# Motor_Driver_New_v21.net
KiCad netlist of a schematic drawn in EAGLE
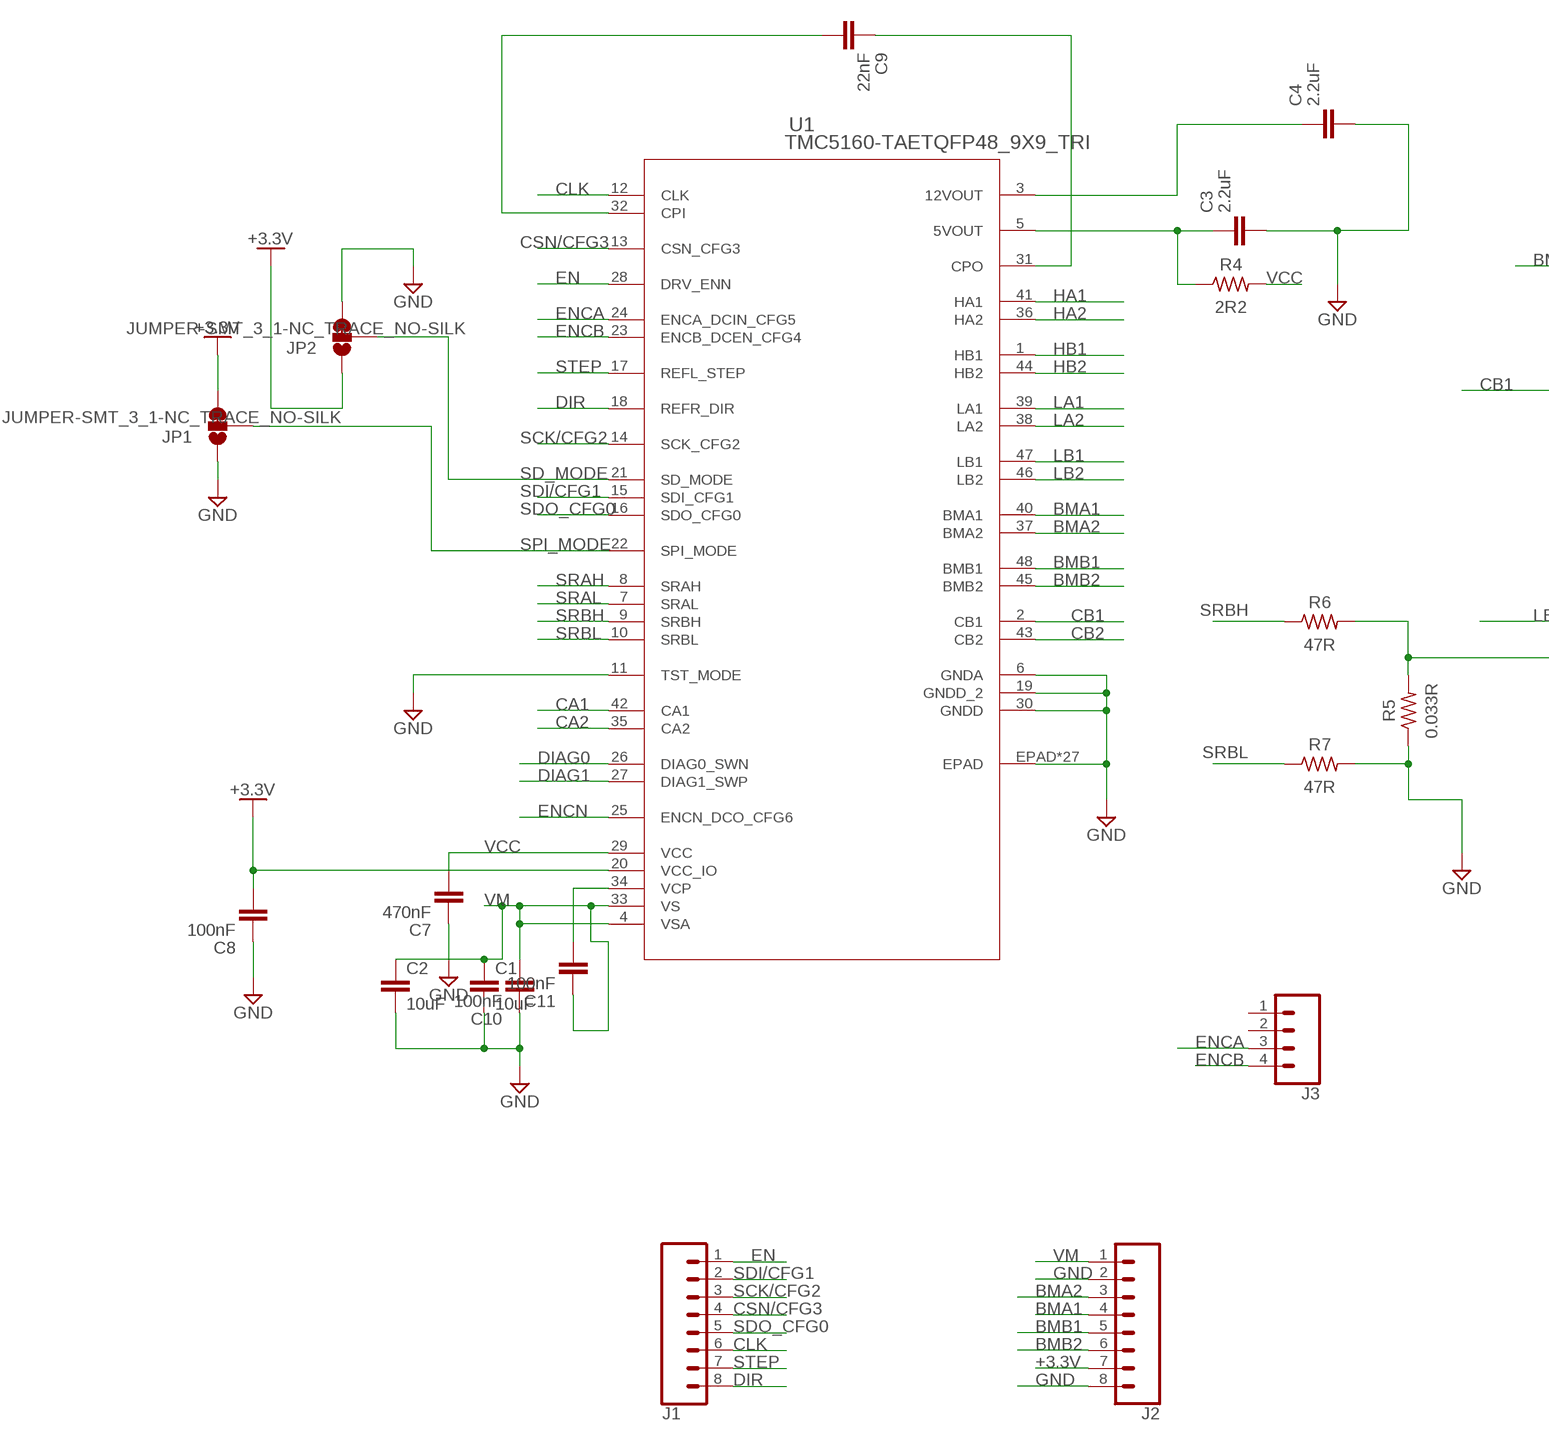
[diagram p0: schematic, sheet 1, part 1 of 2]
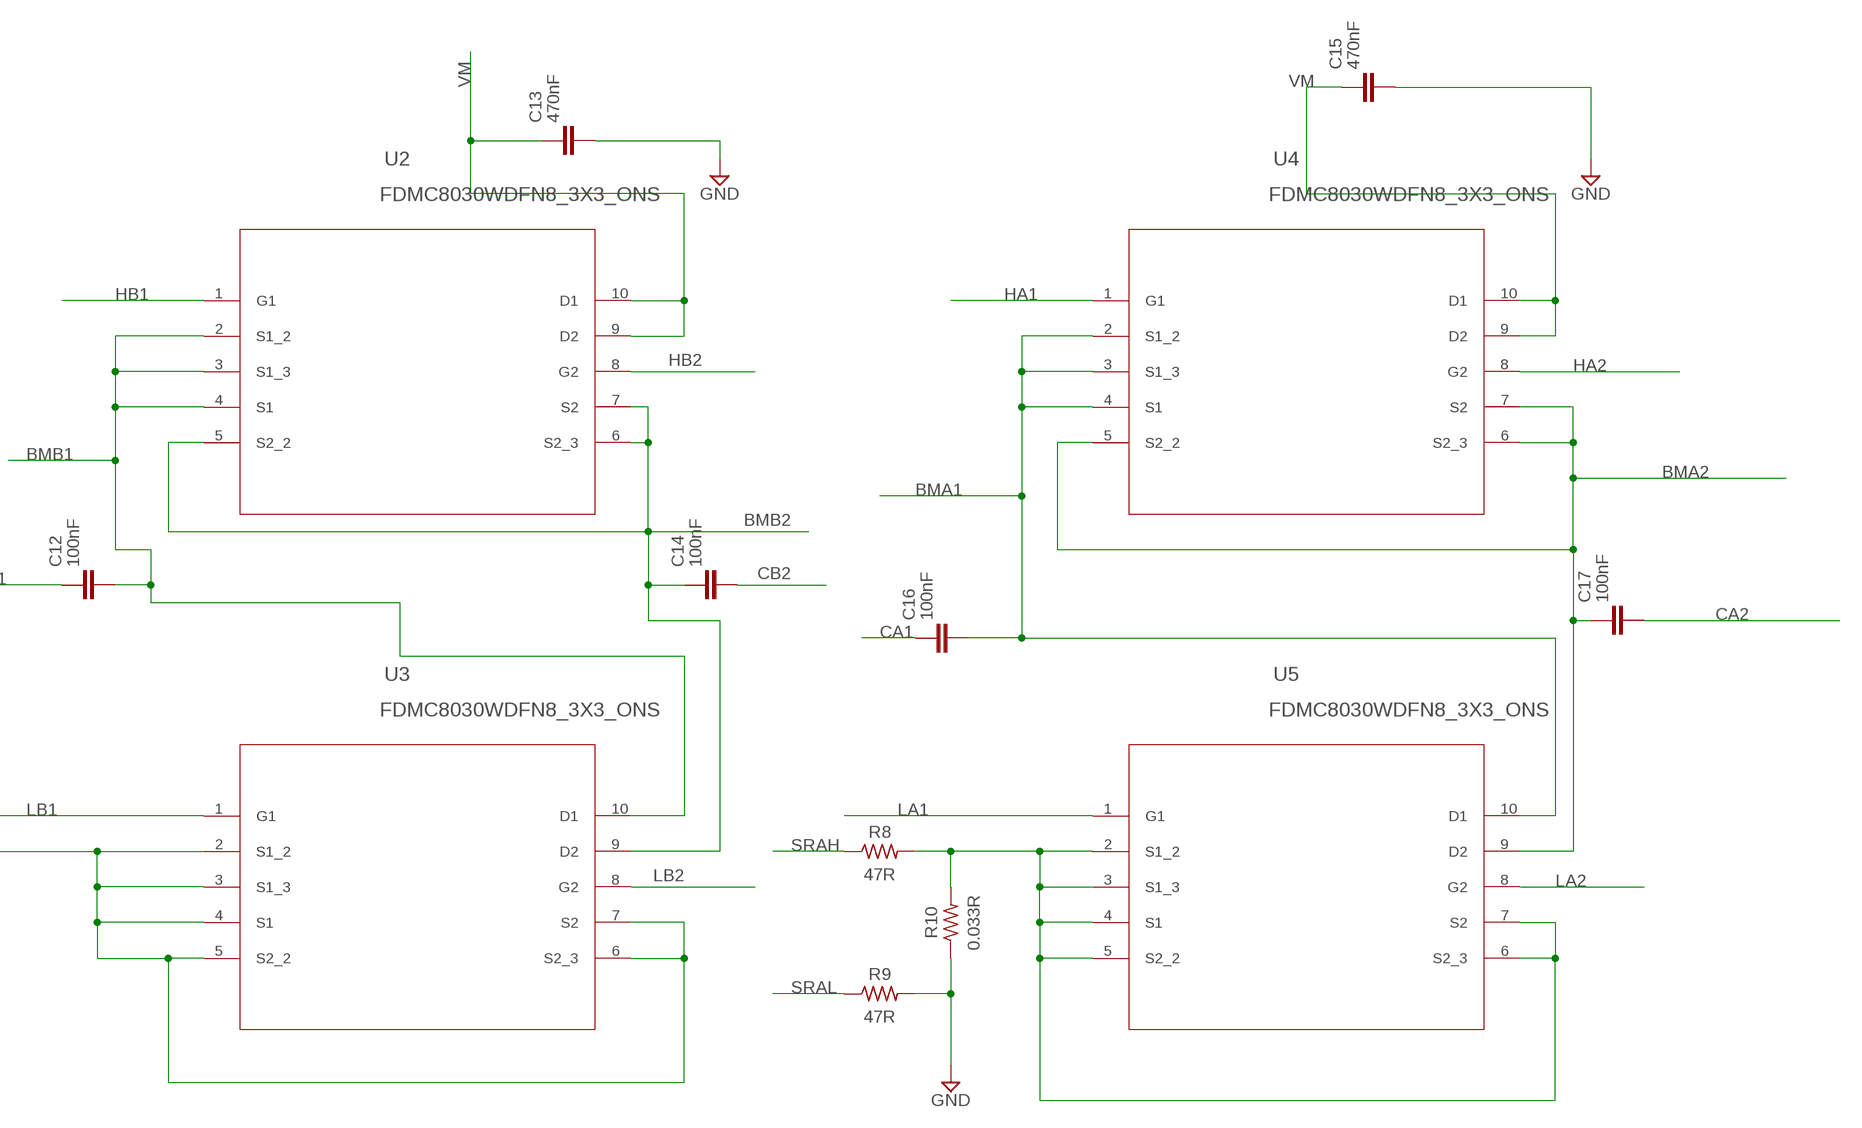
[diagram p1: schematic, sheet 1, part 2 of 2]

(export (version "E")
  (design (tool "Eeschema 10.0.6"))
  (components
    (comp (ref "C1")
      (value "10uF")
      (footprint "eagle-import:0805")
      (libsource (lib "eagle-import") (part "10UF-0805-25V-10%"))
    )
    (comp (ref "C2")
      (value "10uF")
      (footprint "eagle-import:0805")
      (libsource (lib "eagle-import") (part "10UF-0805-25V-10%"))
    )
    (comp (ref "C3")
      (value "2.2uF")
      (footprint "eagle-import:CAPC1005X60")
      (libsource (lib "eagle-import") (part "CCHIP-0402(1005-METRIC)_"))
    )
    (comp (ref "C4")
      (value "2.2uF")
      (footprint "eagle-import:CAPC1005X60")
      (libsource (lib "eagle-import") (part "CCHIP-0402(1005-METRIC)_"))
    )
    (comp (ref "C7")
      (value "470nF")
      (footprint "eagle-import:CAPC1005X60")
      (libsource (lib "eagle-import") (part "CCHIP-0402(1005-METRIC)_"))
    )
    (comp (ref "C8")
      (value "100nF")
      (footprint "eagle-import:CAPC1005X60")
      (libsource (lib "eagle-import") (part "CCHIP-0402(1005-METRIC)_"))
    )
    (comp (ref "C9")
      (value "22nF")
      (footprint "eagle-import:CAPC1005X60")
      (libsource (lib "eagle-import") (part "CCHIP-0402(1005-METRIC)_"))
    )
    (comp (ref "C10")
      (value "100nF")
      (footprint "eagle-import:CAPC1005X60")
      (libsource (lib "eagle-import") (part "CCHIP-0402(1005-METRIC)_"))
    )
    (comp (ref "C11")
      (value "100nF")
      (footprint "eagle-import:CAPC1005X60")
      (libsource (lib "eagle-import") (part "CCHIP-0402(1005-METRIC)_"))
    )
    (comp (ref "C12")
      (value "100nF")
      (footprint "eagle-import:CAPC1005X60")
      (libsource (lib "eagle-import") (part "CCHIP-0402(1005-METRIC)_"))
    )
    (comp (ref "C13")
      (value "470nF")
      (footprint "eagle-import:CAPC1005X60")
      (libsource (lib "eagle-import") (part "CCHIP-0402(1005-METRIC)_"))
    )
    (comp (ref "C14")
      (value "100nF")
      (footprint "eagle-import:CAPC1005X60")
      (libsource (lib "eagle-import") (part "CCHIP-0402(1005-METRIC)_"))
    )
    (comp (ref "C15")
      (value "470nF")
      (footprint "eagle-import:CAPC1005X60")
      (libsource (lib "eagle-import") (part "CCHIP-0402(1005-METRIC)_"))
    )
    (comp (ref "C16")
      (value "100nF")
      (footprint "eagle-import:CAPC1005X60")
      (libsource (lib "eagle-import") (part "CCHIP-0402(1005-METRIC)_"))
    )
    (comp (ref "C17")
      (value "100nF")
      (footprint "eagle-import:CAPC1005X60")
      (libsource (lib "eagle-import") (part "CCHIP-0402(1005-METRIC)_"))
    )
    (comp (ref "J1")
      (value "CONN_08\"")
      (footprint "eagle-import:1X08")
      (libsource (lib "eagle-import") (part "CONN_08{dblquote}"))
    )
    (comp (ref "J2")
      (value "CONN_08\"")
      (footprint "eagle-import:1X08")
      (libsource (lib "eagle-import") (part "CONN_08{dblquote}"))
    )
    (comp (ref "J3")
      (value "CONN_04PTH")
      (footprint "eagle-import:1X04")
      (libsource (lib "eagle-import") (part "CONN_04PTH"))
    )
    (comp (ref "JP1")
      (value "JUMPER-SMT_3_1-NC_TRACE_NO-SILK")
      (footprint "eagle-import:SMT-JUMPER_3_1-NC_TRACE_NO-SILK")
      (libsource (lib "eagle-import") (part "JUMPER-SMT_3_1-NC_TRACE_NO-SILK"))
    )
    (comp (ref "JP2")
      (value "JUMPER-SMT_3_1-NC_TRACE_NO-SILK")
      (footprint "eagle-import:SMT-JUMPER_3_1-NC_TRACE_NO-SILK")
      (libsource (lib "eagle-import") (part "JUMPER-SMT_3_1-NC_TRACE_NO-SILK"))
    )
    (comp (ref "R4")
      (value "2R2")
      (footprint "eagle-import:RESC1005X40")
      (libsource (lib "eagle-import") (part "R-USCHIP-0402(1005-METRIC)_"))
    )
    (comp (ref "R5")
      (value "0.033R")
      (footprint "eagle-import:RESC3216X70")
      (libsource (lib "eagle-import") (part "R-USCHIP-1206(3216-METRIC)_"))
    )
    (comp (ref "R6")
      (value "47R")
      (footprint "eagle-import:RESC1005X40")
      (libsource (lib "eagle-import") (part "R-USCHIP-0402(1005-METRIC)_"))
    )
    (comp (ref "R7")
      (value "47R")
      (footprint "eagle-import:RESC1005X40")
      (libsource (lib "eagle-import") (part "R-USCHIP-0402(1005-METRIC)_"))
    )
    (comp (ref "R8")
      (value "47R")
      (footprint "eagle-import:RESC1005X40")
      (libsource (lib "eagle-import") (part "R-USCHIP-0402(1005-METRIC)_"))
    )
    (comp (ref "R9")
      (value "47R")
      (footprint "eagle-import:RESC1005X40")
      (libsource (lib "eagle-import") (part "R-USCHIP-0402(1005-METRIC)_"))
    )
    (comp (ref "R10")
      (value "0.033R")
      (footprint "eagle-import:RESC3216X70")
      (libsource (lib "eagle-import") (part "R-USCHIP-1206(3216-METRIC)_"))
    )
    (comp (ref "U1")
      (value "TMC5160-TAETQFP48_9X9_TRI")
      (footprint "eagle-import:ETQFP48_9X9_TRI")
      (fields
        (field (name "MANUFACTURER_PART_NUMBER") "TMC5160-TA")
        (field (name "COPYRIGHT") "Copyright (C) 2023 Ultra Librarian. All rights reserved.")
      )
      (libsource (lib "eagle-import") (part "TMC5160-TAETQFP48_9X9_TRI"))
    )
    (comp (ref "U2")
      (value "FDMC8030WDFN8_3X3_ONS")
      (footprint "eagle-import:WDFN8_3X3_ONS")
      (fields
        (field (name "MANUFACTURER_PART_NUMBER") "FDMC8030")
        (field (name "COPYRIGHT") "Copyright (C) 2023 Ultra Librarian. All rights reserved.")
      )
      (libsource (lib "eagle-import") (part "FDMC8030WDFN8_3X3_ONS"))
    )
    (comp (ref "U3")
      (value "FDMC8030WDFN8_3X3_ONS")
      (footprint "eagle-import:WDFN8_3X3_ONS")
      (fields
        (field (name "MANUFACTURER_PART_NUMBER") "FDMC8030")
        (field (name "COPYRIGHT") "Copyright (C) 2023 Ultra Librarian. All rights reserved.")
      )
      (libsource (lib "eagle-import") (part "FDMC8030WDFN8_3X3_ONS"))
    )
    (comp (ref "U4")
      (value "FDMC8030WDFN8_3X3_ONS")
      (footprint "eagle-import:WDFN8_3X3_ONS")
      (fields
        (field (name "MANUFACTURER_PART_NUMBER") "FDMC8030")
        (field (name "COPYRIGHT") "Copyright (C) 2023 Ultra Librarian. All rights reserved.")
      )
      (libsource (lib "eagle-import") (part "FDMC8030WDFN8_3X3_ONS"))
    )
    (comp (ref "U5")
      (value "FDMC8030WDFN8_3X3_ONS")
      (footprint "eagle-import:WDFN8_3X3_ONS")
      (fields
        (field (name "MANUFACTURER_PART_NUMBER") "FDMC8030")
        (field (name "COPYRIGHT") "Copyright (C) 2023 Ultra Librarian. All rights reserved.")
      )
      (libsource (lib "eagle-import") (part "FDMC8030WDFN8_3X3_ONS"))
    )
  )
  (nets
    (net (code "1") (name "+3.3V") (class "Default")
      (node (ref "C8") (pin "2") (pinfunction "2_2") (pintype "passive"))
      (node (ref "J2") (pin "7") (pinfunction "7_7") (pintype "passive"))
      (node (ref "JP1") (pin "3") (pinfunction "3_3") (pintype "passive"))
      (node (ref "JP2") (pin "1") (pinfunction "1_1") (pintype "passive"))
      (node (ref "U1") (pin "20") (pinfunction "VCC_IO_20") (pintype "power_in"))
    )
    (net (code "2") (name "/BMA1") (class "Default")
      (node (ref "C16") (pin "2") (pinfunction "2_2") (pintype "passive"))
      (node (ref "J2") (pin "4") (pinfunction "4_4") (pintype "passive"))
      (node (ref "U1") (pin "40") (pinfunction "BMA1_40") (pintype "passive"))
      (node (ref "U4") (pin "2") (pinfunction "S1_2_2") (pintype "passive"))
      (node (ref "U4") (pin "3") (pinfunction "S1_3_3") (pintype "passive"))
      (node (ref "U4") (pin "4") (pinfunction "S1_4") (pintype "passive"))
      (node (ref "U5") (pin "10") (pinfunction "D1_10") (pintype "passive"))
    )
    (net (code "3") (name "/BMA2") (class "Default")
      (node (ref "C17") (pin "1") (pinfunction "1_1") (pintype "passive"))
      (node (ref "J2") (pin "3") (pinfunction "3_3") (pintype "passive"))
      (node (ref "U1") (pin "37") (pinfunction "BMA2_37") (pintype "passive"))
      (node (ref "U4") (pin "5") (pinfunction "S2_2_5") (pintype "passive"))
      (node (ref "U4") (pin "6") (pinfunction "S2_3_6") (pintype "passive"))
      (node (ref "U4") (pin "7") (pinfunction "S2_7") (pintype "passive"))
      (node (ref "U5") (pin "9") (pinfunction "D2_9") (pintype "passive"))
    )
    (net (code "4") (name "/BMB1") (class "Default")
      (node (ref "C12") (pin "2") (pinfunction "2_2") (pintype "passive"))
      (node (ref "J2") (pin "5") (pinfunction "5_5") (pintype "passive"))
      (node (ref "U1") (pin "48") (pinfunction "BMB1_48") (pintype "passive"))
      (node (ref "U2") (pin "2") (pinfunction "S1_2_2") (pintype "passive"))
      (node (ref "U2") (pin "3") (pinfunction "S1_3_3") (pintype "passive"))
      (node (ref "U2") (pin "4") (pinfunction "S1_4") (pintype "passive"))
      (node (ref "U3") (pin "10") (pinfunction "D1_10") (pintype "passive"))
    )
    (net (code "5") (name "/BMB2") (class "Default")
      (node (ref "C14") (pin "1") (pinfunction "1_1") (pintype "passive"))
      (node (ref "J2") (pin "6") (pinfunction "6_6") (pintype "passive"))
      (node (ref "U1") (pin "45") (pinfunction "BMB2_45") (pintype "passive"))
      (node (ref "U2") (pin "5") (pinfunction "S2_2_5") (pintype "passive"))
      (node (ref "U2") (pin "6") (pinfunction "S2_3_6") (pintype "passive"))
      (node (ref "U2") (pin "7") (pinfunction "S2_7") (pintype "passive"))
      (node (ref "U3") (pin "9") (pinfunction "D2_9") (pintype "passive"))
    )
    (net (code "6") (name "/CA1") (class "Default")
      (node (ref "C16") (pin "1") (pinfunction "1_1") (pintype "passive"))
      (node (ref "U1") (pin "42") (pinfunction "CA1_42") (pintype "passive"))
    )
    (net (code "7") (name "/CA2") (class "Default")
      (node (ref "C17") (pin "2") (pinfunction "2_2") (pintype "passive"))
      (node (ref "U1") (pin "35") (pinfunction "CA2_35") (pintype "passive"))
    )
    (net (code "8") (name "/CB1") (class "Default")
      (node (ref "C12") (pin "1") (pinfunction "1_1") (pintype "passive"))
      (node (ref "U1") (pin "2") (pinfunction "CB1_2") (pintype "passive"))
    )
    (net (code "9") (name "/CB2") (class "Default")
      (node (ref "C14") (pin "2") (pinfunction "2_2") (pintype "passive"))
      (node (ref "U1") (pin "43") (pinfunction "CB2_43") (pintype "passive"))
    )
    (net (code "10") (name "/CLK") (class "Default")
      (node (ref "J1") (pin "6") (pinfunction "6_6") (pintype "passive"))
      (node (ref "U1") (pin "12") (pinfunction "CLK_12") (pintype "input"))
    )
    (net (code "11") (name "/CSN{slash}CFG3") (class "Default")
      (node (ref "J1") (pin "4") (pinfunction "4_4") (pintype "passive"))
      (node (ref "U1") (pin "13") (pinfunction "CSN_CFG3_13") (pintype "input"))
    )
    (net (code "12") (name "/DIAG0") (class "Default")
      (node (ref "U1") (pin "26") (pinfunction "DIAG0_SWN_26") (pintype "bidirectional"))
    )
    (net (code "13") (name "/DIAG1") (class "Default")
      (node (ref "U1") (pin "27") (pinfunction "DIAG1_SWP_27") (pintype "bidirectional"))
    )
    (net (code "14") (name "/DIR") (class "Default")
      (node (ref "J1") (pin "8") (pinfunction "8_8") (pintype "passive"))
      (node (ref "U1") (pin "18") (pinfunction "REFR_DIR_18") (pintype "input"))
    )
    (net (code "15") (name "/EN") (class "Default")
      (node (ref "J1") (pin "1") (pinfunction "1_1") (pintype "passive"))
      (node (ref "U1") (pin "28") (pinfunction "DRV_ENN_28") (pintype "input"))
    )
    (net (code "16") (name "/ENCA") (class "Default")
      (node (ref "J3") (pin "3") (pinfunction "3_3") (pintype "passive"))
      (node (ref "U1") (pin "24") (pinfunction "ENCA_DCIN_CFG5_24") (pintype "input"))
    )
    (net (code "17") (name "/ENCB") (class "Default")
      (node (ref "J3") (pin "4") (pinfunction "4_4") (pintype "passive"))
      (node (ref "U1") (pin "23") (pinfunction "ENCB_DCEN_CFG4_23") (pintype "input"))
    )
    (net (code "18") (name "/ENCN") (class "Default")
      (node (ref "U1") (pin "25") (pinfunction "ENCN_DCO_CFG6_25") (pintype "bidirectional"))
    )
    (net (code "19") (name "/HA1") (class "Default")
      (node (ref "U1") (pin "41") (pinfunction "HA1_41") (pintype "output"))
      (node (ref "U4") (pin "1") (pinfunction "G1_1") (pintype "passive"))
    )
    (net (code "20") (name "/HA2") (class "Default")
      (node (ref "U1") (pin "36") (pinfunction "HA2_36") (pintype "output"))
      (node (ref "U4") (pin "8") (pinfunction "G2_8") (pintype "passive"))
    )
    (net (code "21") (name "/HB1") (class "Default")
      (node (ref "U1") (pin "1") (pinfunction "HB1_1") (pintype "output"))
      (node (ref "U2") (pin "1") (pinfunction "G1_1") (pintype "passive"))
    )
    (net (code "22") (name "/HB2") (class "Default")
      (node (ref "U1") (pin "44") (pinfunction "HB2_44") (pintype "output"))
      (node (ref "U2") (pin "8") (pinfunction "G2_8") (pintype "passive"))
    )
    (net (code "23") (name "/LA1") (class "Default")
      (node (ref "U1") (pin "39") (pinfunction "LA1_39") (pintype "output"))
      (node (ref "U5") (pin "1") (pinfunction "G1_1") (pintype "passive"))
    )
    (net (code "24") (name "/LA2") (class "Default")
      (node (ref "U1") (pin "38") (pinfunction "LA2_38") (pintype "output"))
      (node (ref "U5") (pin "8") (pinfunction "G2_8") (pintype "passive"))
    )
    (net (code "25") (name "/LB1") (class "Default")
      (node (ref "U1") (pin "47") (pinfunction "LB1_47") (pintype "output"))
      (node (ref "U3") (pin "1") (pinfunction "G1_1") (pintype "passive"))
    )
    (net (code "26") (name "/LB2") (class "Default")
      (node (ref "U1") (pin "46") (pinfunction "LB2_46") (pintype "output"))
      (node (ref "U3") (pin "8") (pinfunction "G2_8") (pintype "passive"))
    )
    (net (code "27") (name "/SCK{slash}CFG2") (class "Default")
      (node (ref "J1") (pin "3") (pinfunction "3_3") (pintype "passive"))
      (node (ref "U1") (pin "14") (pinfunction "SCK_CFG2_14") (pintype "input"))
    )
    (net (code "28") (name "/SDI{slash}CFG1") (class "Default")
      (node (ref "J1") (pin "2") (pinfunction "2_2") (pintype "passive"))
      (node (ref "U1") (pin "15") (pinfunction "SDI_CFG1_15") (pintype "input"))
    )
    (net (code "29") (name "/SDO_CFG0") (class "Default")
      (node (ref "J1") (pin "5") (pinfunction "5_5") (pintype "passive"))
      (node (ref "U1") (pin "16") (pinfunction "SDO_CFG0_16") (pintype "input"))
    )
    (net (code "30") (name "/SD_MODE") (class "Default")
      (node (ref "JP2") (pin "2") (pinfunction "2_2") (pintype "passive"))
      (node (ref "U1") (pin "21") (pinfunction "SD_MODE_21") (pintype "input"))
    )
    (net (code "31") (name "/SPI_MODE") (class "Default")
      (node (ref "JP1") (pin "2") (pinfunction "2_2") (pintype "passive"))
      (node (ref "U1") (pin "22") (pinfunction "SPI_MODE_22") (pintype "input"))
    )
    (net (code "32") (name "/SRAH") (class "Default")
      (node (ref "R8") (pin "1") (pinfunction "1_1") (pintype "passive"))
      (node (ref "U1") (pin "8") (pinfunction "SRAH_8") (pintype "input"))
    )
    (net (code "33") (name "/SRAL") (class "Default")
      (node (ref "R9") (pin "1") (pinfunction "1_1") (pintype "passive"))
      (node (ref "U1") (pin "7") (pinfunction "SRAL_7") (pintype "input"))
    )
    (net (code "34") (name "/SRBH") (class "Default")
      (node (ref "R6") (pin "1") (pinfunction "1_1") (pintype "passive"))
      (node (ref "U1") (pin "9") (pinfunction "SRBH_9") (pintype "input"))
    )
    (net (code "35") (name "/SRBL") (class "Default")
      (node (ref "R7") (pin "1") (pinfunction "1_1") (pintype "passive"))
      (node (ref "U1") (pin "10") (pinfunction "SRBL_10") (pintype "input"))
    )
    (net (code "36") (name "/STEP") (class "Default")
      (node (ref "J1") (pin "7") (pinfunction "7_7") (pintype "passive"))
      (node (ref "U1") (pin "17") (pinfunction "REFL_STEP_17") (pintype "input"))
    )
    (net (code "37") (name "/VCC") (class "Default")
      (node (ref "C7") (pin "2") (pinfunction "2_2") (pintype "passive"))
      (node (ref "R4") (pin "2") (pinfunction "2_2") (pintype "passive"))
      (node (ref "U1") (pin "29") (pinfunction "VCC_29") (pintype "power_in"))
    )
    (net (code "38") (name "/VM") (class "Default")
      (node (ref "C1") (pin "1") (pinfunction "1_1") (pintype "passive"))
      (node (ref "C10") (pin "2") (pinfunction "2_2") (pintype "passive"))
      (node (ref "C11") (pin "1") (pinfunction "1_1") (pintype "passive"))
      (node (ref "C13") (pin "1") (pinfunction "1_1") (pintype "passive"))
      (node (ref "C15") (pin "1") (pinfunction "1_1") (pintype "passive"))
      (node (ref "C2") (pin "1") (pinfunction "1_1") (pintype "passive"))
      (node (ref "J2") (pin "1") (pinfunction "1_1") (pintype "passive"))
      (node (ref "U1") (pin "33") (pinfunction "VS_33") (pintype "power_in"))
      (node (ref "U1") (pin "4") (pinfunction "VSA_4") (pintype "power_in"))
      (node (ref "U2") (pin "10") (pinfunction "D1_10") (pintype "passive"))
      (node (ref "U2") (pin "9") (pinfunction "D2_9") (pintype "passive"))
      (node (ref "U4") (pin "10") (pinfunction "D1_10") (pintype "passive"))
      (node (ref "U4") (pin "9") (pinfunction "D2_9") (pintype "passive"))
    )
    (net (code "39") (name "GND") (class "Default")
      (node (ref "C1") (pin "2") (pinfunction "2_2") (pintype "passive"))
      (node (ref "C10") (pin "1") (pinfunction "1_1") (pintype "passive"))
      (node (ref "C13") (pin "2") (pinfunction "2_2") (pintype "passive"))
      (node (ref "C15") (pin "2") (pinfunction "2_2") (pintype "passive"))
      (node (ref "C2") (pin "2") (pinfunction "2_2") (pintype "passive"))
      (node (ref "C3") (pin "2") (pinfunction "2_2") (pintype "passive"))
      (node (ref "C4") (pin "2") (pinfunction "2_2") (pintype "passive"))
      (node (ref "C7") (pin "1") (pinfunction "1_1") (pintype "passive"))
      (node (ref "C8") (pin "1") (pinfunction "1_1") (pintype "passive"))
      (node (ref "J2") (pin "2") (pinfunction "2_2") (pintype "passive"))
      (node (ref "J2") (pin "8") (pinfunction "8_8") (pintype "passive"))
      (node (ref "JP1") (pin "1") (pinfunction "1_1") (pintype "passive"))
      (node (ref "JP2") (pin "3") (pinfunction "3_3") (pintype "passive"))
      (node (ref "R10") (pin "1") (pinfunction "1_1") (pintype "passive"))
      (node (ref "R5") (pin "1") (pinfunction "1_1") (pintype "passive"))
      (node (ref "R7") (pin "2") (pinfunction "2_2") (pintype "passive"))
      (node (ref "R9") (pin "2") (pinfunction "2_2") (pintype "passive"))
      (node (ref "U1") (pin "11") (pinfunction "TST_MODE_11") (pintype "input"))
      (node (ref "U1") (pin "19") (pinfunction "GNDD_2_19") (pintype "power_in"))
      (node (ref "U1") (pin "30") (pinfunction "GNDD_30") (pintype "power_in"))
      (node (ref "U1") (pin "6") (pinfunction "GNDA_6") (pintype "power_in"))
      (node (ref "U1") (pin "EPAD") (pinfunction "EPAD_EPAD") (pintype "passive"))
      (node (ref "U1") (pin "EPAD1") (pinfunction "EPAD_EPAD1") (pintype "passive"))
      (node (ref "U1") (pin "P$1") (pinfunction "EPAD_P$1") (pintype "passive"))
      (node (ref "U1") (pin "P$10") (pinfunction "EPAD_P$10") (pintype "passive"))
      (node (ref "U1") (pin "P$11") (pinfunction "EPAD_P$11") (pintype "passive"))
      (node (ref "U1") (pin "P$12") (pinfunction "EPAD_P$12") (pintype "passive"))
      (node (ref "U1") (pin "P$13") (pinfunction "EPAD_P$13") (pintype "passive"))
      (node (ref "U1") (pin "P$14") (pinfunction "EPAD_P$14") (pintype "passive"))
      (node (ref "U1") (pin "P$15") (pinfunction "EPAD_P$15") (pintype "passive"))
      (node (ref "U1") (pin "P$16") (pinfunction "EPAD_P$16") (pintype "passive"))
      (node (ref "U1") (pin "P$17") (pinfunction "EPAD_P$17") (pintype "passive"))
      (node (ref "U1") (pin "P$18") (pinfunction "EPAD_P$18") (pintype "passive"))
      (node (ref "U1") (pin "P$19") (pinfunction "EPAD_P$19") (pintype "passive"))
      (node (ref "U1") (pin "P$2") (pinfunction "EPAD_P$2") (pintype "passive"))
      (node (ref "U1") (pin "P$20") (pinfunction "EPAD_P$20") (pintype "passive"))
      (node (ref "U1") (pin "P$21") (pinfunction "EPAD_P$21") (pintype "passive"))
      (node (ref "U1") (pin "P$22") (pinfunction "EPAD_P$22") (pintype "passive"))
      (node (ref "U1") (pin "P$23") (pinfunction "EPAD_P$23") (pintype "passive"))
      (node (ref "U1") (pin "P$24") (pinfunction "EPAD_P$24") (pintype "passive"))
      (node (ref "U1") (pin "P$25") (pinfunction "EPAD_P$25") (pintype "passive"))
      (node (ref "U1") (pin "P$3") (pinfunction "EPAD_P$3") (pintype "passive"))
      (node (ref "U1") (pin "P$4") (pinfunction "EPAD_P$4") (pintype "passive"))
      (node (ref "U1") (pin "P$5") (pinfunction "EPAD_P$5") (pintype "passive"))
      (node (ref "U1") (pin "P$6") (pinfunction "EPAD_P$6") (pintype "passive"))
      (node (ref "U1") (pin "P$7") (pinfunction "EPAD_P$7") (pintype "passive"))
      (node (ref "U1") (pin "P$8") (pinfunction "EPAD_P$8") (pintype "passive"))
      (node (ref "U1") (pin "P$9") (pinfunction "EPAD_P$9") (pintype "passive"))
    )
    (net (code "40") (name "Net-(U1-5VOUT)") (class "Default")
      (node (ref "C3") (pin "1") (pinfunction "1_1") (pintype "passive"))
      (node (ref "R4") (pin "1") (pinfunction "1_1") (pintype "passive"))
      (node (ref "U1") (pin "5") (pinfunction "5VOUT_5") (pintype "output"))
    )
    (net (code "41") (name "Net-(U1-12VOUT)") (class "Default")
      (node (ref "C4") (pin "1") (pinfunction "1_1") (pintype "passive"))
      (node (ref "U1") (pin "3") (pinfunction "12VOUT_3") (pintype "output"))
    )
    (net (code "42") (name "Net-(U1-CPI)") (class "Default")
      (node (ref "C9") (pin "2") (pinfunction "2_2") (pintype "passive"))
      (node (ref "U1") (pin "32") (pinfunction "CPI_32") (pintype "input"))
    )
    (net (code "43") (name "Net-(U1-CPO)") (class "Default")
      (node (ref "C9") (pin "1") (pinfunction "1_1") (pintype "passive"))
      (node (ref "U1") (pin "31") (pinfunction "CPO_31") (pintype "output"))
    )
    (net (code "44") (name "Net-(U1-VCP)") (class "Default")
      (node (ref "C11") (pin "2") (pinfunction "2_2") (pintype "passive"))
      (node (ref "U1") (pin "34") (pinfunction "VCP_34") (pintype "power_in"))
    )
    (net (code "45") (name "Net-(U3-S1)") (class "Default")
      (node (ref "R5") (pin "2") (pinfunction "2_2") (pintype "passive"))
      (node (ref "R6") (pin "2") (pinfunction "2_2") (pintype "passive"))
      (node (ref "U3") (pin "2") (pinfunction "S1_2_2") (pintype "passive"))
      (node (ref "U3") (pin "3") (pinfunction "S1_3_3") (pintype "passive"))
      (node (ref "U3") (pin "4") (pinfunction "S1_4") (pintype "passive"))
      (node (ref "U3") (pin "5") (pinfunction "S2_2_5") (pintype "passive"))
      (node (ref "U3") (pin "6") (pinfunction "S2_3_6") (pintype "passive"))
      (node (ref "U3") (pin "7") (pinfunction "S2_7") (pintype "passive"))
    )
    (net (code "46") (name "Net-(U5-S1)") (class "Default")
      (node (ref "R10") (pin "2") (pinfunction "2_2") (pintype "passive"))
      (node (ref "R8") (pin "2") (pinfunction "2_2") (pintype "passive"))
      (node (ref "U5") (pin "2") (pinfunction "S1_2_2") (pintype "passive"))
      (node (ref "U5") (pin "3") (pinfunction "S1_3_3") (pintype "passive"))
      (node (ref "U5") (pin "4") (pinfunction "S1_4") (pintype "passive"))
      (node (ref "U5") (pin "5") (pinfunction "S2_2_5") (pintype "passive"))
      (node (ref "U5") (pin "6") (pinfunction "S2_3_6") (pintype "passive"))
      (node (ref "U5") (pin "7") (pinfunction "S2_7") (pintype "passive"))
    )
    (net (code "47") (name "unconnected-(J3-Pad1)") (class "Default")
      (node (ref "J3") (pin "1") (pinfunction "1_1") (pintype "passive"))
    )
    (net (code "48") (name "unconnected-(J3-Pad2)") (class "Default")
      (node (ref "J3") (pin "2") (pinfunction "2_2") (pintype "passive"))
    )
  )
)
